# Sheet2.net
KiCad netlist of a schematic drawn in Altium Designer
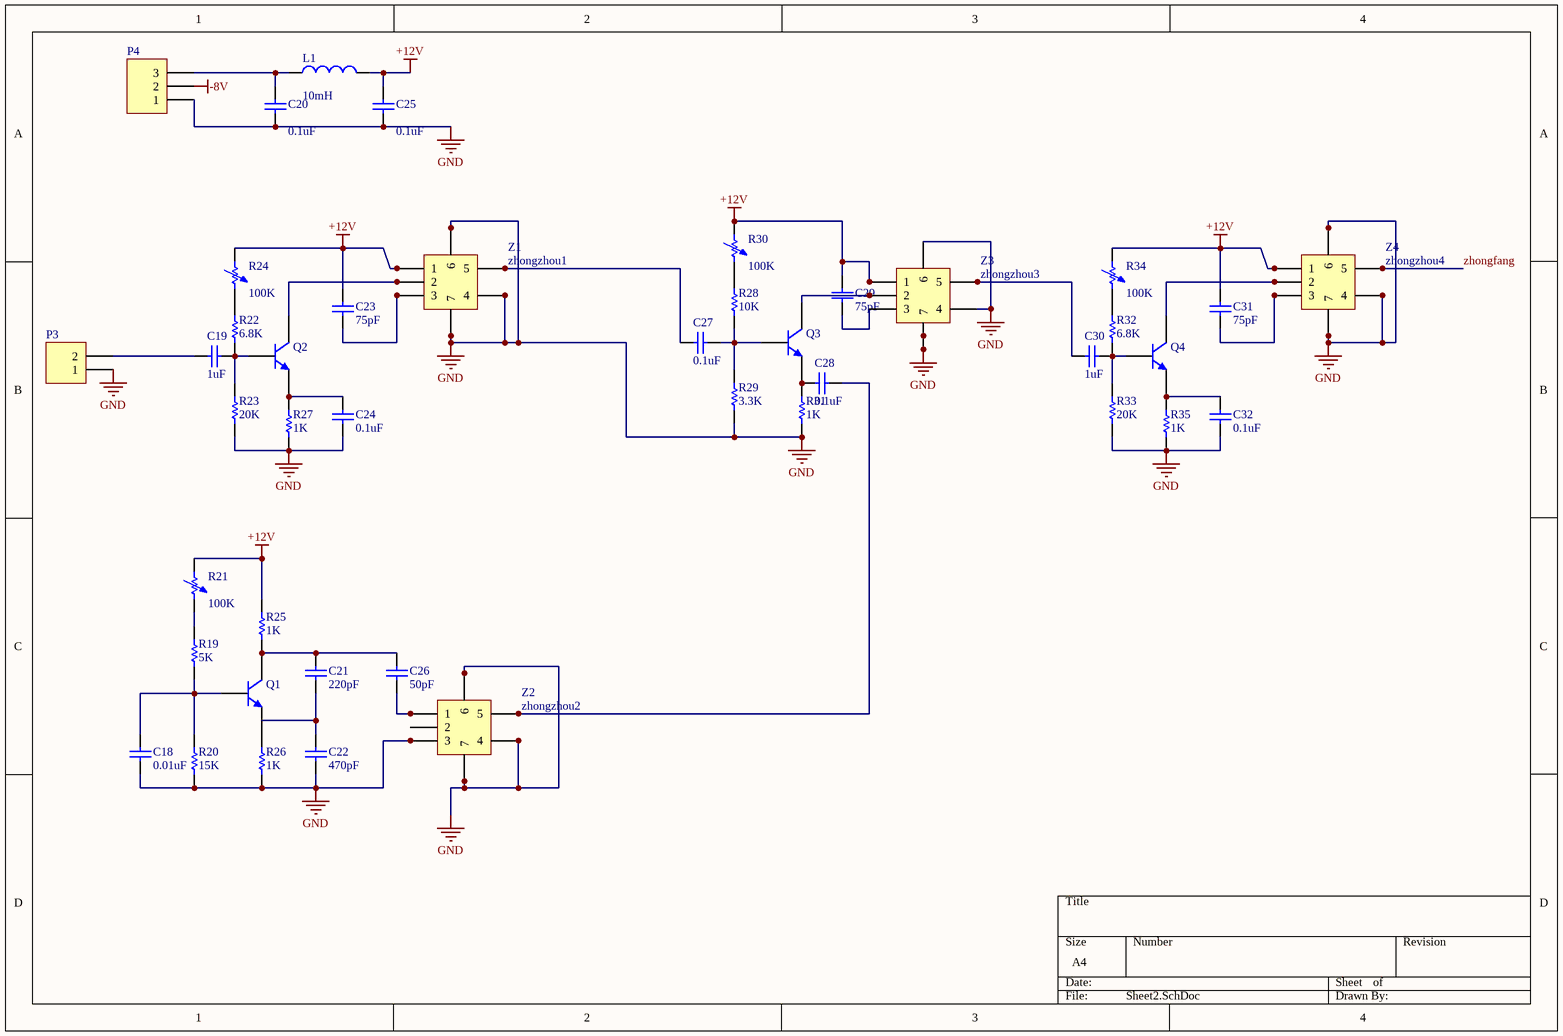
[diagram p0: Sheet2.SchDoc]

(export (version "E")
  (design (tool "Eeschema 10.0.6"))
  (components
    (comp (ref "C18")
      (value "0.01uF")
      (footprint "2012[0805]")
      (description "Capacitor")
      (fields (field (name "Comment") "Cap") (field (name "PUBLISHER") "Altium Limited"))
      (libsource (lib "Miscellaneous Devices") (part "Cap"))
    )
    (comp (ref "C19")
      (value "1uF")
      (footprint "2012[0805]")
      (description "Capacitor")
      (fields (field (name "Comment") "Cap") (field (name "PUBLISHER") "Altium Limited"))
      (libsource (lib "Miscellaneous Devices") (part "Cap"))
    )
    (comp (ref "C20")
      (value "0.1uF")
      (footprint "2012[0805]")
      (description "Capacitor")
      (fields (field (name "Comment") "Cap") (field (name "PUBLISHER") "Altium Limited"))
      (libsource (lib "Miscellaneous Devices") (part "Cap"))
    )
    (comp (ref "C21")
      (value "220pF")
      (footprint "2012[0805]")
      (description "Capacitor")
      (fields (field (name "Comment") "Cap") (field (name "PUBLISHER") "Altium Limited"))
      (libsource (lib "Miscellaneous Devices") (part "Cap"))
    )
    (comp (ref "C22")
      (value "470pF")
      (footprint "2012[0805]")
      (description "Capacitor")
      (fields (field (name "Comment") "Cap") (field (name "PUBLISHER") "Altium Limited"))
      (libsource (lib "Miscellaneous Devices") (part "Cap"))
    )
    (comp (ref "C23")
      (value "75pF")
      (footprint "2012[0805]")
      (description "Capacitor")
      (fields (field (name "Comment") "Cap") (field (name "PUBLISHER") "Altium Limited"))
      (libsource (lib "Miscellaneous Devices") (part "Cap"))
    )
    (comp (ref "C24")
      (value "0.1uF")
      (footprint "2012[0805]")
      (description "Capacitor")
      (fields (field (name "Comment") "Cap") (field (name "PUBLISHER") "Altium Limited"))
      (libsource (lib "Miscellaneous Devices") (part "Cap"))
    )
    (comp (ref "C25")
      (value "0.1uF")
      (footprint "2012[0805]")
      (description "Capacitor")
      (fields (field (name "Comment") "Cap") (field (name "PUBLISHER") "Altium Limited"))
      (libsource (lib "Miscellaneous Devices") (part "Cap"))
    )
    (comp (ref "C26")
      (value "50pF")
      (footprint "2012[0805]")
      (description "Capacitor")
      (fields (field (name "Comment") "Cap") (field (name "PUBLISHER") "Altium Limited"))
      (libsource (lib "Miscellaneous Devices") (part "Cap"))
    )
    (comp (ref "C27")
      (value "0.1uF")
      (footprint "2012[0805]")
      (description "Capacitor")
      (fields (field (name "Comment") "Cap") (field (name "PUBLISHER") "Altium Limited"))
      (libsource (lib "Miscellaneous Devices") (part "Cap"))
    )
    (comp (ref "C28")
      (value "0.1uF")
      (footprint "2012[0805]")
      (description "Capacitor")
      (fields (field (name "Comment") "Cap") (field (name "PUBLISHER") "Altium Limited"))
      (libsource (lib "Miscellaneous Devices") (part "Cap"))
    )
    (comp (ref "C29")
      (value "75pF")
      (footprint "2012[0805]")
      (description "Capacitor")
      (fields (field (name "Comment") "Cap") (field (name "PUBLISHER") "Altium Limited"))
      (libsource (lib "Miscellaneous Devices") (part "Cap"))
    )
    (comp (ref "C30")
      (value "1uF")
      (footprint "2012[0805]")
      (description "Capacitor")
      (fields (field (name "Comment") "Cap") (field (name "PUBLISHER") "Altium Limited"))
      (libsource (lib "Miscellaneous Devices") (part "Cap"))
    )
    (comp (ref "C31")
      (value "75pF")
      (footprint "2012[0805]")
      (description "Capacitor")
      (fields (field (name "Comment") "Cap") (field (name "PUBLISHER") "Altium Limited"))
      (libsource (lib "Miscellaneous Devices") (part "Cap"))
    )
    (comp (ref "C32")
      (value "0.1uF")
      (footprint "2012[0805]")
      (description "Capacitor")
      (fields (field (name "Comment") "Cap") (field (name "PUBLISHER") "Altium Limited"))
      (libsource (lib "Miscellaneous Devices") (part "Cap"))
    )
    (comp (ref "L1")
      (value "10mH")
      (footprint "2012[0805]")
      (description "Inductor")
      (fields (field (name "PUBLISHER") "Altium Limited"))
      (libsource (lib "Miscellaneous Devices") (part "Inductor"))
    )
    (comp (ref "P3")
      (value "Header 2")
      (footprint "HDR1X2")
      (description "Header, 2-Pin")
      (fields (field (name "PUBLISHER") "Altium Limited"))
      (libsource (lib "Miscellaneous Connectors") (part "Header 2"))
    )
    (comp (ref "P4")
      (value "Header 3")
      (footprint "shuru")
      (description "Header, 3-Pin")
      (fields (field (name "PUBLISHER") "Altium Limited"))
      (libsource (lib "Miscellaneous Connectors") (part "Header 3"))
    )
    (comp (ref "Q1")
      (value "NPN")
      (footprint "TO-226")
      (description "NPN Bipolar Transistor")
      (fields (field (name "PUBLISHER") "Altium Limited"))
      (libsource (lib "Miscellaneous Devices") (part "NPN"))
    )
    (comp (ref "Q2")
      (value "NPN")
      (footprint "TO-226")
      (description "NPN Bipolar Transistor")
      (fields (field (name "PUBLISHER") "Altium Limited"))
      (libsource (lib "Miscellaneous Devices") (part "NPN"))
    )
    (comp (ref "Q3")
      (value "NPN")
      (footprint "TO-226")
      (description "NPN Bipolar Transistor")
      (fields (field (name "PUBLISHER") "Altium Limited"))
      (libsource (lib "Miscellaneous Devices") (part "NPN"))
    )
    (comp (ref "Q4")
      (value "NPN")
      (footprint "TO-226")
      (description "NPN Bipolar Transistor")
      (fields (field (name "PUBLISHER") "Altium Limited"))
      (libsource (lib "Miscellaneous Devices") (part "NPN"))
    )
    (comp (ref "R19")
      (value "5K")
      (footprint "2012[0805]")
      (description "Resistor")
      (fields (field (name "Comment") "Res1") (field (name "PUBLISHER") "Altium Limited"))
      (libsource (lib "Miscellaneous Devices") (part "Res1"))
    )
    (comp (ref "R20")
      (value "15K")
      (footprint "2012[0805]")
      (description "Resistor")
      (fields (field (name "Comment") "Res1") (field (name "PUBLISHER") "Altium Limited"))
      (libsource (lib "Miscellaneous Devices") (part "Res1"))
    )
    (comp (ref "R21")
      (value "100K")
      (footprint "2012[0805]")
      (description "Variable Resistor")
      (fields (field (name "Comment") "Res Adj1") (field (name "PUBLISHER") "Altium Limited"))
      (libsource (lib "Miscellaneous Devices") (part "Res Adj1"))
    )
    (comp (ref "R22")
      (value "6.8K")
      (footprint "2012[0805]")
      (description "Resistor")
      (fields (field (name "Comment") "Res1") (field (name "PUBLISHER") "Altium Limited"))
      (libsource (lib "Miscellaneous Devices") (part "Res1"))
    )
    (comp (ref "R23")
      (value "20K")
      (footprint "2012[0805]")
      (description "Resistor")
      (fields (field (name "Comment") "Res1") (field (name "PUBLISHER") "Altium Limited"))
      (libsource (lib "Miscellaneous Devices") (part "Res1"))
    )
    (comp (ref "R24")
      (value "100K")
      (footprint "2012[0805]")
      (description "Variable Resistor")
      (fields (field (name "Comment") "Res Adj1") (field (name "PUBLISHER") "Altium Limited"))
      (libsource (lib "Miscellaneous Devices") (part "Res Adj1"))
    )
    (comp (ref "R25")
      (value "1K")
      (footprint "2012[0805]")
      (description "Resistor")
      (fields (field (name "Comment") "Res1") (field (name "PUBLISHER") "Altium Limited"))
      (libsource (lib "Miscellaneous Devices") (part "Res1"))
    )
    (comp (ref "R26")
      (value "1K")
      (footprint "2012[0805]")
      (description "Resistor")
      (fields (field (name "Comment") "Res1") (field (name "PUBLISHER") "Altium Limited"))
      (libsource (lib "Miscellaneous Devices") (part "Res1"))
    )
    (comp (ref "R27")
      (value "1K")
      (footprint "2012[0805]")
      (description "Resistor")
      (fields (field (name "Comment") "Res1") (field (name "PUBLISHER") "Altium Limited"))
      (libsource (lib "Miscellaneous Devices") (part "Res1"))
    )
    (comp (ref "R28")
      (value "10K")
      (footprint "2012[0805]")
      (description "Resistor")
      (fields (field (name "Comment") "Res1") (field (name "PUBLISHER") "Altium Limited"))
      (libsource (lib "Miscellaneous Devices") (part "Res1"))
    )
    (comp (ref "R29")
      (value "3.3K")
      (footprint "2012[0805]")
      (description "Resistor")
      (fields (field (name "Comment") "Res1") (field (name "PUBLISHER") "Altium Limited"))
      (libsource (lib "Miscellaneous Devices") (part "Res1"))
    )
    (comp (ref "R30")
      (value "100K")
      (footprint "2012[0805]")
      (description "Variable Resistor")
      (fields (field (name "Comment") "Res Adj1") (field (name "PUBLISHER") "Altium Limited"))
      (libsource (lib "Miscellaneous Devices") (part "Res Adj1"))
    )
    (comp (ref "R31")
      (value "1K")
      (footprint "2012[0805]")
      (description "Resistor")
      (fields (field (name "Comment") "Res1") (field (name "PUBLISHER") "Altium Limited"))
      (libsource (lib "Miscellaneous Devices") (part "Res1"))
    )
    (comp (ref "R32")
      (value "6.8K")
      (footprint "2012[0805]")
      (description "Resistor")
      (fields (field (name "Comment") "Res1") (field (name "PUBLISHER") "Altium Limited"))
      (libsource (lib "Miscellaneous Devices") (part "Res1"))
    )
    (comp (ref "R33")
      (value "20K")
      (footprint "2012[0805]")
      (description "Resistor")
      (fields (field (name "Comment") "Res1") (field (name "PUBLISHER") "Altium Limited"))
      (libsource (lib "Miscellaneous Devices") (part "Res1"))
    )
    (comp (ref "R34")
      (value "100K")
      (footprint "2012[0805]")
      (description "Variable Resistor")
      (fields (field (name "Comment") "Res Adj1") (field (name "PUBLISHER") "Altium Limited"))
      (libsource (lib "Miscellaneous Devices") (part "Res Adj1"))
    )
    (comp (ref "R35")
      (value "1K")
      (footprint "2012[0805]")
      (description "Resistor")
      (fields (field (name "Comment") "Res1") (field (name "PUBLISHER") "Altium Limited"))
      (libsource (lib "Miscellaneous Devices") (part "Res1"))
    )
    (comp (ref "Z1")
      (value "zhongzhou1")
      (footprint "zhongzhou")
      (libsource (lib "Schlib1") (part "zhongzhou1"))
    )
    (comp (ref "Z2")
      (value "zhongzhou2")
      (footprint "zhongzhou")
      (libsource (lib "Schlib1") (part "zhongzhou2"))
    )
    (comp (ref "Z3")
      (value "zhongzhou3")
      (footprint "zhongzhou")
      (libsource (lib "Schlib1") (part "zhongzhou3"))
    )
    (comp (ref "Z4")
      (value "zhongzhou4")
      (footprint "zhongzhou")
      (libsource (lib "Schlib1") (part "zhongzhou4"))
    )
  )
  (nets
    (net (code "1") (name "+12V") (class "Default")
      (node (ref "C23") (pin "1") (pinfunction "1_1") (pintype "passive"))
      (node (ref "C25") (pin "2") (pinfunction "2_2") (pintype "passive"))
      (node (ref "C29") (pin "1") (pinfunction "1_1") (pintype "passive"))
      (node (ref "C31") (pin "1") (pinfunction "1_1") (pintype "passive"))
      (node (ref "L1") (pin "2") (pinfunction "2_2") (pintype "passive"))
      (node (ref "R21") (pin "1") (pinfunction "1_1") (pintype "passive"))
      (node (ref "R24") (pin "1") (pinfunction "1_1") (pintype "passive"))
      (node (ref "R25") (pin "2") (pinfunction "2_2") (pintype "passive"))
      (node (ref "R30") (pin "1") (pinfunction "1_1") (pintype "passive"))
      (node (ref "R34") (pin "1") (pinfunction "1_1") (pintype "passive"))
      (node (ref "Z1") (pin "1") (pinfunction "1_1") (pintype "passive"))
      (node (ref "Z3") (pin "1") (pinfunction "1_1") (pintype "passive"))
      (node (ref "Z4") (pin "1") (pinfunction "1_1") (pintype "passive"))
    )
    (net (code "2") (name "-8V") (class "Default")
      (node (ref "P4") (pin "2") (pinfunction "2_2") (pintype "passive"))
    )
    (net (code "3") (name "/zhongfang") (class "Default")
      (node (ref "Z4") (pin "5") (pinfunction "5_5") (pintype "passive"))
    )
    (net (code "4") (name "GND") (class "Default")
      (node (ref "C18") (pin "2") (pinfunction "2_2") (pintype "passive"))
      (node (ref "C20") (pin "1") (pinfunction "1_1") (pintype "passive"))
      (node (ref "C22") (pin "2") (pinfunction "2_2") (pintype "passive"))
      (node (ref "C24") (pin "1") (pinfunction "1_1") (pintype "passive"))
      (node (ref "C25") (pin "1") (pinfunction "1_1") (pintype "passive"))
      (node (ref "C32") (pin "1") (pinfunction "1_1") (pintype "passive"))
      (node (ref "P3") (pin "1") (pinfunction "1_1") (pintype "passive"))
      (node (ref "P4") (pin "1") (pinfunction "1_1") (pintype "passive"))
      (node (ref "R20") (pin "1") (pinfunction "1_1") (pintype "passive"))
      (node (ref "R23") (pin "1") (pinfunction "1_1") (pintype "passive"))
      (node (ref "R26") (pin "1") (pinfunction "1_1") (pintype "passive"))
      (node (ref "R27") (pin "1") (pinfunction "1_1") (pintype "passive"))
      (node (ref "R29") (pin "1") (pinfunction "1_1") (pintype "passive"))
      (node (ref "R31") (pin "1") (pinfunction "1_1") (pintype "passive"))
      (node (ref "R33") (pin "1") (pinfunction "1_1") (pintype "passive"))
      (node (ref "R35") (pin "1") (pinfunction "1_1") (pintype "passive"))
      (node (ref "Z1") (pin "4") (pinfunction "4_4") (pintype "passive"))
      (node (ref "Z1") (pin "6") (pinfunction "6_6") (pintype "passive"))
      (node (ref "Z1") (pin "7") (pinfunction "7_7") (pintype "passive"))
      (node (ref "Z2") (pin "3") (pinfunction "3_3") (pintype "passive"))
      (node (ref "Z2") (pin "4") (pinfunction "4_4") (pintype "passive"))
      (node (ref "Z2") (pin "6") (pinfunction "6_6") (pintype "passive"))
      (node (ref "Z2") (pin "7") (pinfunction "7_7") (pintype "passive"))
      (node (ref "Z3") (pin "4") (pinfunction "4_4") (pintype "passive"))
      (node (ref "Z3") (pin "6") (pinfunction "6_6") (pintype "passive"))
      (node (ref "Z3") (pin "7") (pinfunction "7_7") (pintype "passive"))
      (node (ref "Z4") (pin "4") (pinfunction "4_4") (pintype "passive"))
      (node (ref "Z4") (pin "6") (pinfunction "6_6") (pintype "passive"))
      (node (ref "Z4") (pin "7") (pinfunction "7_7") (pintype "passive"))
    )
    (net (code "5") (name "Net-(C19-Pad1)") (class "Default")
      (node (ref "C19") (pin "1") (pinfunction "1_1") (pintype "passive"))
      (node (ref "P3") (pin "2") (pinfunction "2_2") (pintype "passive"))
    )
    (net (code "6") (name "Net-(C20-Pad2)") (class "Default")
      (node (ref "C20") (pin "2") (pinfunction "2_2") (pintype "passive"))
      (node (ref "L1") (pin "1") (pinfunction "1_1") (pintype "passive"))
      (node (ref "P4") (pin "3") (pinfunction "3_3") (pintype "passive"))
    )
    (net (code "7") (name "Net-(C21-Pad2)") (class "Default")
      (node (ref "C21") (pin "2") (pinfunction "2_2") (pintype "passive"))
      (node (ref "C22") (pin "1") (pinfunction "1_1") (pintype "passive"))
    )
    (net (code "8") (name "Net-(C23-Pad2)") (class "Default")
      (node (ref "C23") (pin "2") (pinfunction "2_2") (pintype "passive"))
      (node (ref "Z1") (pin "3") (pinfunction "3_3") (pintype "passive"))
    )
    (net (code "9") (name "Net-(C26-Pad1)") (class "Default")
      (node (ref "C26") (pin "1") (pinfunction "1_1") (pintype "passive"))
      (node (ref "Z2") (pin "1") (pinfunction "1_1") (pintype "passive"))
    )
    (net (code "10") (name "Net-(C27-Pad1)") (class "Default")
      (node (ref "C27") (pin "1") (pinfunction "1_1") (pintype "passive"))
      (node (ref "Z1") (pin "5") (pinfunction "5_5") (pintype "passive"))
    )
    (net (code "11") (name "Net-(C28-Pad2)") (class "Default")
      (node (ref "C28") (pin "2") (pinfunction "2_2") (pintype "passive"))
      (node (ref "Z2") (pin "5") (pinfunction "5_5") (pintype "passive"))
    )
    (net (code "12") (name "Net-(C29-Pad2)") (class "Default")
      (node (ref "C29") (pin "2") (pinfunction "2_2") (pintype "passive"))
      (node (ref "Z3") (pin "3") (pinfunction "3_3") (pintype "passive"))
    )
    (net (code "13") (name "Net-(C30-Pad1)") (class "Default")
      (node (ref "C30") (pin "1") (pinfunction "1_1") (pintype "passive"))
      (node (ref "Z3") (pin "5") (pinfunction "5_5") (pintype "passive"))
    )
    (net (code "14") (name "Net-(C31-Pad2)") (class "Default")
      (node (ref "C31") (pin "2") (pinfunction "2_2") (pintype "passive"))
      (node (ref "Z4") (pin "3") (pinfunction "3_3") (pintype "passive"))
    )
    (net (code "15") (name "Net-(Q1-B)") (class "Default")
      (node (ref "C18") (pin "1") (pinfunction "1_1") (pintype "passive"))
      (node (ref "Q1") (pin "2") (pinfunction "B_2") (pintype "passive"))
      (node (ref "R19") (pin "1") (pinfunction "1_1") (pintype "passive"))
      (node (ref "R20") (pin "2") (pinfunction "2_2") (pintype "passive"))
    )
    (net (code "16") (name "Net-(Q1-C)") (class "Default")
      (node (ref "C21") (pin "1") (pinfunction "1_1") (pintype "passive"))
      (node (ref "C26") (pin "2") (pinfunction "2_2") (pintype "passive"))
      (node (ref "Q1") (pin "1") (pinfunction "C_1") (pintype "passive"))
      (node (ref "R25") (pin "1") (pinfunction "1_1") (pintype "passive"))
    )
    (net (code "17") (name "Net-(Q1-E)") (class "Default")
      (node (ref "Q1") (pin "3") (pinfunction "E_3") (pintype "passive"))
      (node (ref "R26") (pin "2") (pinfunction "2_2") (pintype "passive"))
    )
    (net (code "18") (name "Net-(Q2-B)") (class "Default")
      (node (ref "C19") (pin "2") (pinfunction "2_2") (pintype "passive"))
      (node (ref "Q2") (pin "2") (pinfunction "B_2") (pintype "passive"))
      (node (ref "R22") (pin "1") (pinfunction "1_1") (pintype "passive"))
      (node (ref "R23") (pin "2") (pinfunction "2_2") (pintype "passive"))
    )
    (net (code "19") (name "Net-(Q2-C)") (class "Default")
      (node (ref "Q2") (pin "1") (pinfunction "C_1") (pintype "passive"))
      (node (ref "Z1") (pin "2") (pinfunction "2_2") (pintype "passive"))
    )
    (net (code "20") (name "Net-(Q2-E)") (class "Default")
      (node (ref "C24") (pin "2") (pinfunction "2_2") (pintype "passive"))
      (node (ref "Q2") (pin "3") (pinfunction "E_3") (pintype "passive"))
      (node (ref "R27") (pin "2") (pinfunction "2_2") (pintype "passive"))
    )
    (net (code "21") (name "Net-(Q3-B)") (class "Default")
      (node (ref "C27") (pin "2") (pinfunction "2_2") (pintype "passive"))
      (node (ref "Q3") (pin "2") (pinfunction "B_2") (pintype "passive"))
      (node (ref "R28") (pin "1") (pinfunction "1_1") (pintype "passive"))
      (node (ref "R29") (pin "2") (pinfunction "2_2") (pintype "passive"))
    )
    (net (code "22") (name "Net-(Q3-C)") (class "Default")
      (node (ref "Q3") (pin "1") (pinfunction "C_1") (pintype "passive"))
      (node (ref "Z3") (pin "2") (pinfunction "2_2") (pintype "passive"))
    )
    (net (code "23") (name "Net-(Q3-E)") (class "Default")
      (node (ref "C28") (pin "1") (pinfunction "1_1") (pintype "passive"))
      (node (ref "Q3") (pin "3") (pinfunction "E_3") (pintype "passive"))
      (node (ref "R31") (pin "2") (pinfunction "2_2") (pintype "passive"))
    )
    (net (code "24") (name "Net-(Q4-B)") (class "Default")
      (node (ref "C30") (pin "2") (pinfunction "2_2") (pintype "passive"))
      (node (ref "Q4") (pin "2") (pinfunction "B_2") (pintype "passive"))
      (node (ref "R32") (pin "1") (pinfunction "1_1") (pintype "passive"))
      (node (ref "R33") (pin "2") (pinfunction "2_2") (pintype "passive"))
    )
    (net (code "25") (name "Net-(Q4-C)") (class "Default")
      (node (ref "Q4") (pin "1") (pinfunction "C_1") (pintype "passive"))
      (node (ref "Z4") (pin "2") (pinfunction "2_2") (pintype "passive"))
    )
    (net (code "26") (name "Net-(Q4-E)") (class "Default")
      (node (ref "C32") (pin "2") (pinfunction "2_2") (pintype "passive"))
      (node (ref "Q4") (pin "3") (pinfunction "E_3") (pintype "passive"))
      (node (ref "R35") (pin "2") (pinfunction "2_2") (pintype "passive"))
    )
    (net (code "27") (name "Net-(R19-Pad2)") (class "Default")
      (node (ref "R19") (pin "2") (pinfunction "2_2") (pintype "passive"))
      (node (ref "R21") (pin "2") (pinfunction "2_2") (pintype "passive"))
    )
    (net (code "28") (name "Net-(R22-Pad2)") (class "Default")
      (node (ref "R22") (pin "2") (pinfunction "2_2") (pintype "passive"))
      (node (ref "R24") (pin "2") (pinfunction "2_2") (pintype "passive"))
    )
    (net (code "29") (name "Net-(R28-Pad2)") (class "Default")
      (node (ref "R28") (pin "2") (pinfunction "2_2") (pintype "passive"))
      (node (ref "R30") (pin "2") (pinfunction "2_2") (pintype "passive"))
    )
    (net (code "30") (name "Net-(R32-Pad2)") (class "Default")
      (node (ref "R32") (pin "2") (pinfunction "2_2") (pintype "passive"))
      (node (ref "R34") (pin "2") (pinfunction "2_2") (pintype "passive"))
    )
    (net (code "31") (name "unconnected-(Z2-Pad2)") (class "Default")
      (node (ref "Z2") (pin "2") (pinfunction "2_2") (pintype "passive"))
    )
  )
)
